# TemperatureZB.net
KiCad netlist of a schematic drawn in Altium Designer
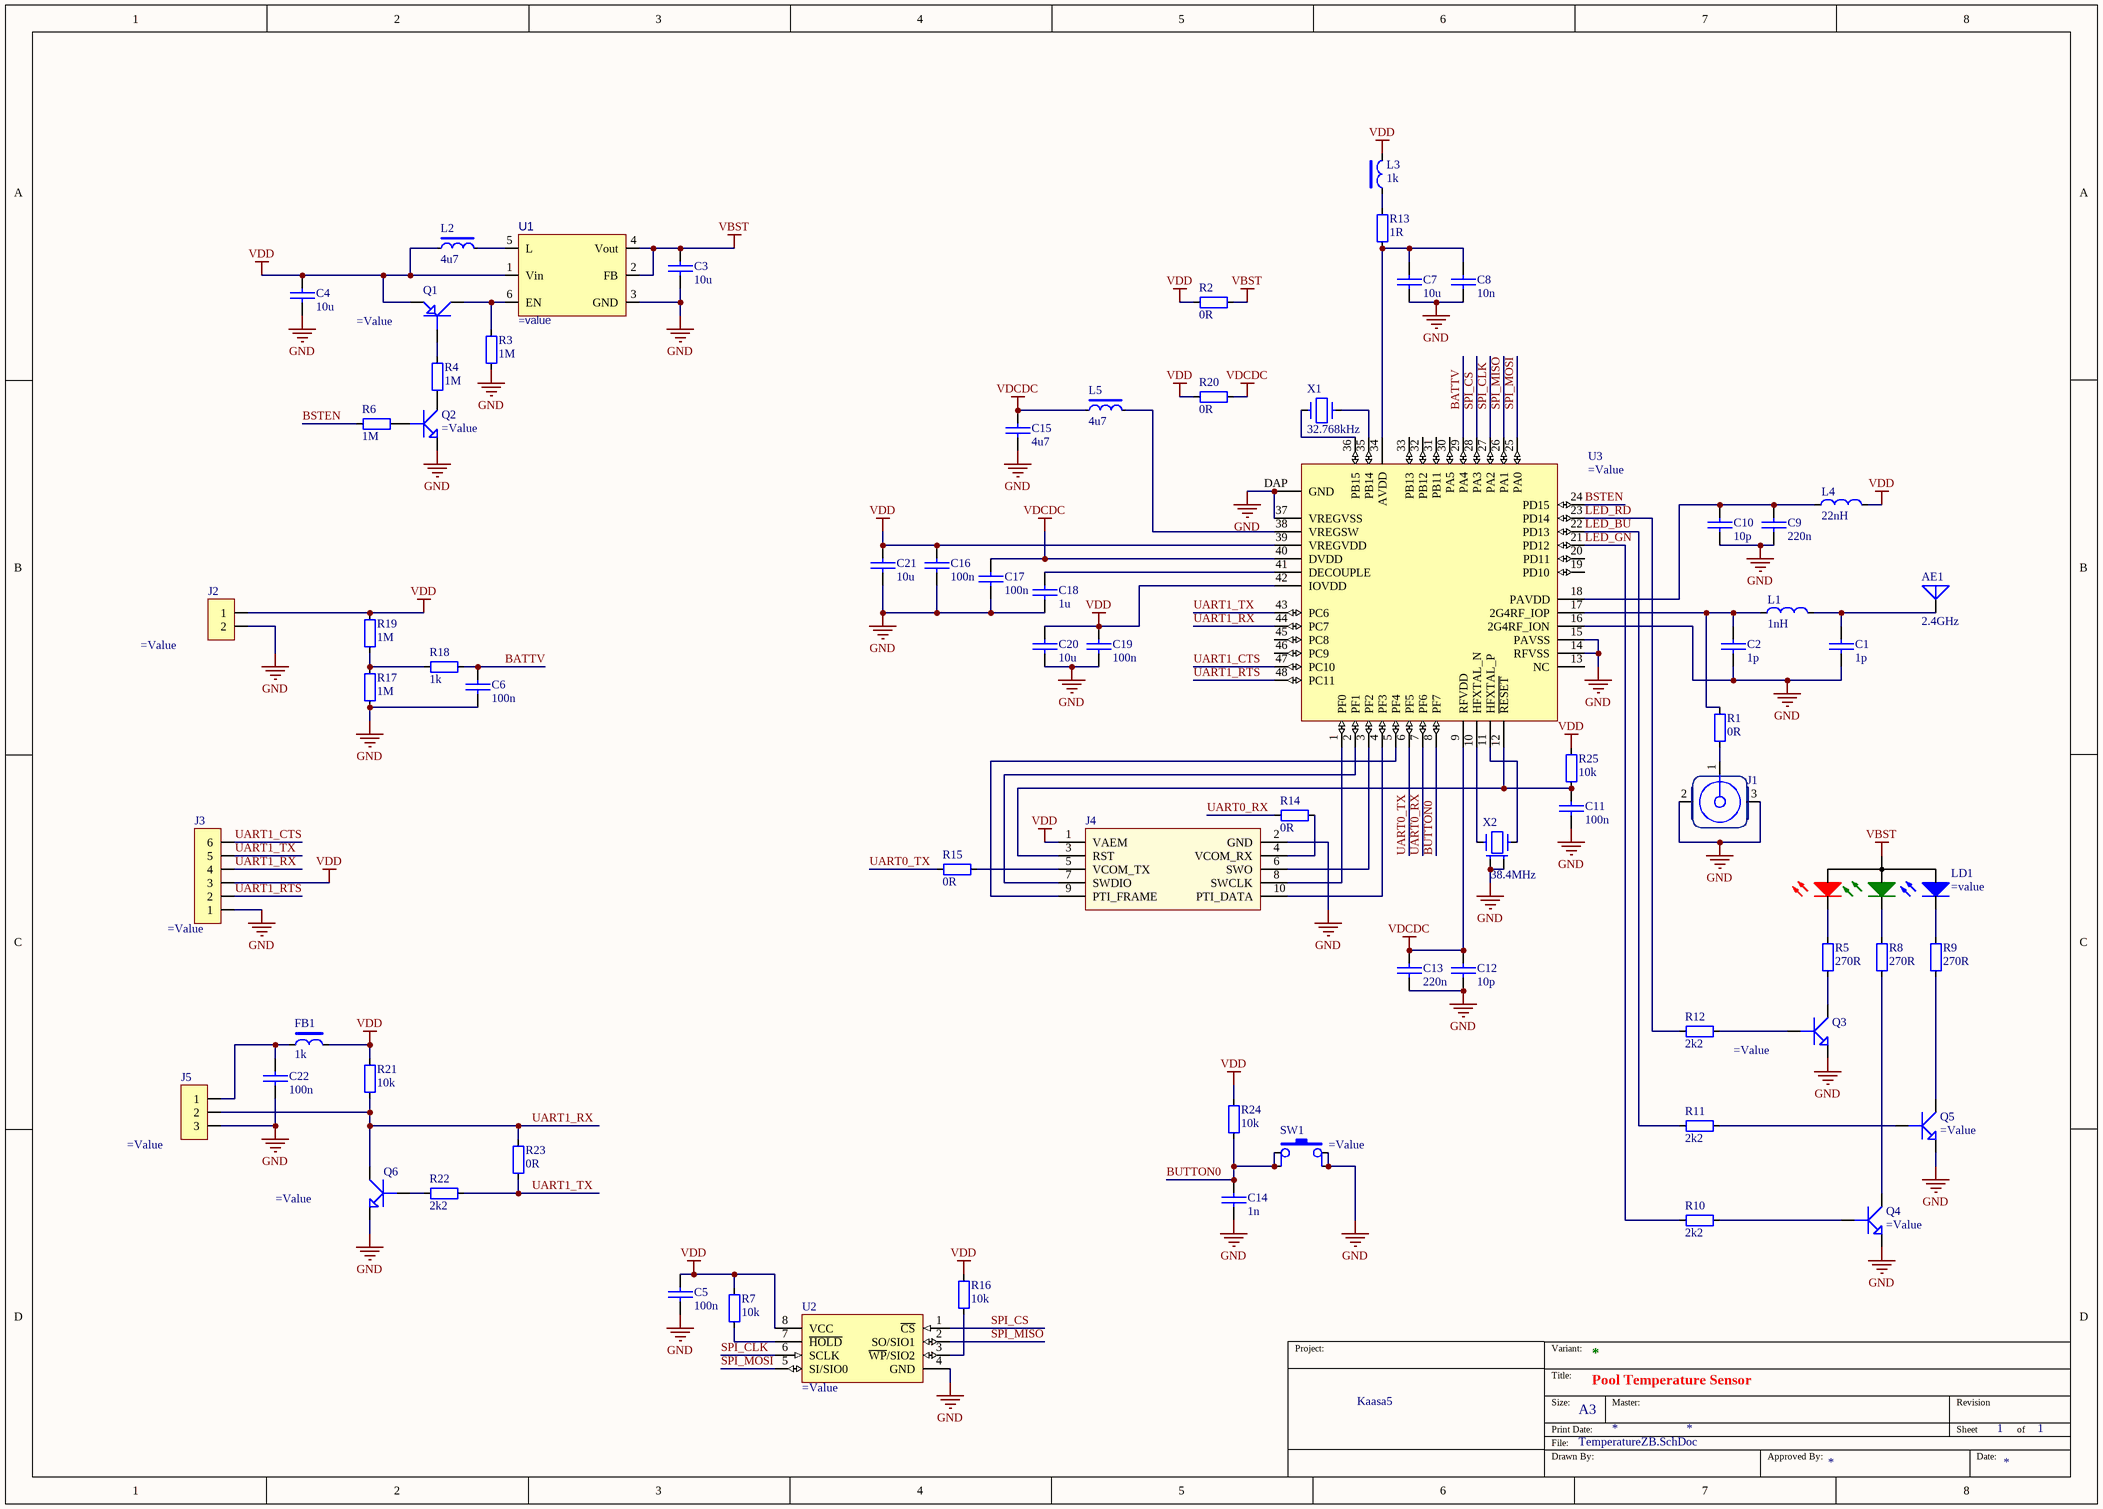
[diagram p0: TemperatureZB.SchDoc]

(export (version "E")
  (design (tool "Eeschema 10.0.6"))
  (components
    (comp (ref "AE1")
      (value "2.4GHz")
      (footprint "ANT2450AT45A100")
      (description "ANT SMD CER 1dB 3808")
      (fields
        (field (name "MANUFACTURER") "Johanson Technology Inc.")
        (field (name "PART NUMBER") "2450AT45A100E")
      )
      (libsource (lib "kaasa5") (part "AE_NORM"))
    )
    (comp (ref "C1")
      (value "1p")
      (footprint "CAPC1005X06N")
      (description "CAP SMD CER C0G/NPO ±0.1p 50V 0402")
      (fields (field (name "PART NUMBER") "CC0402BRNPO9BN1R0") (field (name "MANUFACTURER") "Yageo"))
      (libsource (lib "kaasa5") (part "C_NORM"))
    )
    (comp (ref "C2")
      (value "1p")
      (footprint "CAPC1005X06N")
      (description "CAP SMD CER C0G/NPO ±0.1p 50V 0402")
      (fields (field (name "PART NUMBER") "CC0402BRNPO9BN1R0") (field (name "MANUFACTURER") "Yageo"))
      (libsource (lib "kaasa5") (part "C_NORM"))
    )
    (comp (ref "C3")
      (value "10u")
      (footprint "CAPC1005X06N")
      (description "CAP SMD CER X5R 20% 6.3V 0402")
      (fields
        (field (name "PART NUMBER") "GRM155R60J106ME15D")
        (field (name "MANUFACTURER") "Murata Electronics")
      )
      (libsource (lib "kaasa5") (part "C_NORM"))
    )
    (comp (ref "C4")
      (value "10u")
      (footprint "CAPC1005X06N")
      (description "CAP SMD CER X5R 20% 6.3V 0402")
      (fields
        (field (name "PART NUMBER") "GRM155R60J106ME15D")
        (field (name "MANUFACTURER") "Murata Electronics")
      )
      (libsource (lib "kaasa5") (part "C_NORM"))
    )
    (comp (ref "C5")
      (value "100n")
      (footprint "CAPC1005X06N")
      (description "CAP SMD CER X7R 10% 16V 0402")
      (fields (field (name "PART NUMBER") "CC0402KRX7R7BB104") (field (name "MANUFACTURER") "Yageo"))
      (libsource (lib "kaasa5") (part "C_NORM"))
    )
    (comp (ref "C6")
      (value "100n")
      (footprint "CAPC1005X06N")
      (description "CAP SMD CER X7R 10% 16V 0402")
      (fields (field (name "MANUFACTURER") "Yageo") (field (name "PART NUMBER") "CC0402KRX7R7BB104"))
      (libsource (lib "kaasa5") (part "C_NORM"))
    )
    (comp (ref "C7")
      (value "10u")
      (footprint "CAPC1005X06N")
      (description "CAP SMD CER X5R 20% 6.3V 0402")
      (fields
        (field (name "PART NUMBER") "GRM155R60J106ME15D")
        (field (name "MANUFACTURER") "Murata Electronics")
      )
      (libsource (lib "kaasa5") (part "C_NORM"))
    )
    (comp (ref "C8")
      (value "10n")
      (footprint "CAPC1005X06N")
      (description "CAP SMD CER X7R 10% 50V 0402")
      (fields (field (name "PART NUMBER") "CC0402KRX7R9BB103") (field (name "MANUFACTURER") "Yageo"))
      (libsource (lib "kaasa5") (part "C_NORM"))
    )
    (comp (ref "C9")
      (value "220n")
      (footprint "CAPC1005X06N")
      (description "CAP SMD CER X7R 10% 16V 0402")
      (fields
        (field (name "PART NUMBER") "CL05B224KO5NNNC")
        (field (name "MANUFACTURER") "Samsung Electro-Mechanics")
      )
      (libsource (lib "kaasa5") (part "C_NORM"))
    )
    (comp (ref "C10")
      (value "10p")
      (footprint "CAPC1005X06N")
      (description "CAP SMD CER C0G/NPO 5% 50V 0402")
      (fields (field (name "PART NUMBER") "CC0402JRNPO9BN100") (field (name "MANUFACTURER") "Yageo"))
      (libsource (lib "kaasa5") (part "C_NORM"))
    )
    (comp (ref "C11")
      (value "100n")
      (footprint "CAPC1005X06N")
      (description "CAP SMD CER X7R 10% 16V 0402")
      (fields (field (name "PART NUMBER") "CC0402KRX7R7BB104") (field (name "MANUFACTURER") "Yageo"))
      (libsource (lib "kaasa5") (part "C_NORM"))
    )
    (comp (ref "C12")
      (value "10p")
      (footprint "CAPC1005X06N")
      (description "CAP SMD CER C0G/NPO 5% 50V 0402")
      (fields (field (name "PART NUMBER") "CC0402JRNPO9BN100") (field (name "MANUFACTURER") "Yageo"))
      (libsource (lib "kaasa5") (part "C_NORM"))
    )
    (comp (ref "C13")
      (value "220n")
      (footprint "CAPC1005X06N")
      (description "CAP SMD CER X7R 10% 16V 0402")
      (fields
        (field (name "PART NUMBER") "CL05B224KO5NNNC")
        (field (name "MANUFACTURER") "Samsung Electro-Mechanics")
      )
      (libsource (lib "kaasa5") (part "C_NORM"))
    )
    (comp (ref "C14")
      (value "1n")
      (footprint "CAPC1005X06N")
      (description "CAP SMD CER C0G/NPO 5% 50V 0402")
      (fields
        (field (name "PART NUMBER") "GRM1555C1H102JA01D")
        (field (name "MANUFACTURER") "Murata Electronics")
      )
      (libsource (lib "kaasa5") (part "C_NORM"))
    )
    (comp (ref "C15")
      (value "4u7")
      (footprint "CAPC1608X09N")
      (description "CAP SMD CER X7R 10% 6V3 0603")
      (fields
        (field (name "PART NUMBER") "CL10B475KQ8NQNC")
        (field (name "MANUFACTURER") "Samsung Electro-Mechanics")
      )
      (libsource (lib "kaasa5") (part "C_NORM"))
    )
    (comp (ref "C16")
      (value "100n")
      (footprint "CAPC1005X06N")
      (description "CAP SMD CER X7R 10% 16V 0402")
      (fields (field (name "PART NUMBER") "CC0402KRX7R7BB104") (field (name "MANUFACTURER") "Yageo"))
      (libsource (lib "kaasa5") (part "C_NORM"))
    )
    (comp (ref "C17")
      (value "100n")
      (footprint "CAPC1005X06N")
      (description "CAP SMD CER X7R 10% 16V 0402")
      (fields (field (name "PART NUMBER") "CC0402KRX7R7BB104") (field (name "MANUFACTURER") "Yageo"))
      (libsource (lib "kaasa5") (part "C_NORM"))
    )
    (comp (ref "C18")
      (value "1u")
      (footprint "CAPC1005X06N")
      (description "CAP SMD CER X7R 10% 6.3V 0402")
      (fields
        (field (name "PART NUMBER") "GRM155R70J105KA12J")
        (field (name "MANUFACTURER") "Murata Electronics")
      )
      (libsource (lib "kaasa5") (part "C_NORM"))
    )
    (comp (ref "C19")
      (value "100n")
      (footprint "CAPC1005X06N")
      (description "CAP SMD CER X7R 10% 16V 0402")
      (fields (field (name "PART NUMBER") "CC0402KRX7R7BB104") (field (name "MANUFACTURER") "Yageo"))
      (libsource (lib "kaasa5") (part "C_NORM"))
    )
    (comp (ref "C20")
      (value "10u")
      (footprint "CAPC1005X06N")
      (description "CAP SMD CER X5R 20% 6.3V 0402")
      (fields
        (field (name "PART NUMBER") "GRM155R60J106ME15D")
        (field (name "MANUFACTURER") "Murata Electronics")
      )
      (libsource (lib "kaasa5") (part "C_NORM"))
    )
    (comp (ref "C21")
      (value "10u")
      (footprint "CAPC1005X06N")
      (description "CAP SMD CER X5R 20% 6.3V 0402")
      (fields
        (field (name "PART NUMBER") "GRM155R60J106ME15D")
        (field (name "MANUFACTURER") "Murata Electronics")
      )
      (libsource (lib "kaasa5") (part "C_NORM"))
    )
    (comp (ref "C22")
      (value "100n")
      (footprint "CAPC1005X06N")
      (description "CAP SMD CER X7R 10% 16V 0402")
      (fields (field (name "MANUFACTURER") "Yageo") (field (name "PART NUMBER") "CC0402KRX7R7BB104"))
      (libsource (lib "kaasa5") (part "C_NORM"))
    )
    (comp (ref "FB1")
      (value "1k")
      (footprint "INDC1005X06N")
      (description "FER BEAD SMD ±25% 300mA 0402")
      (fields (field (name "PART NUMBER") "BK1005HS102-T") (field (name "MANUFACTURER") "Taiyo Yuden"))
      (libsource (lib "kaasa5") (part "FB_BEAD"))
    )
    (comp (ref "J1")
      (value "~")
      (footprint "U.FL-LP(V)-040")
      (description "CON SMD VERT RF U.FL")
      (fields
        (field (name "PART NUMBER") "1909763-1")
        (field (name "MANUFACTURER") "TE Connectivity AMP Connectors")
      )
      (libsource (lib "kaasa5") (part "J_CON_UFL"))
    )
    (comp (ref "J2")
      (value "~")
      (footprint "S2B-PH-SM4-TB")
      (description "CON SMD RIGHT ANGLE 100V 2A 2x5pin")
      (fields
        (field (name "MANUFACTURER") "JST Sales America Inc.")
        (field (name "PART NUMBER") "S2B-PH-SM4-TB(LF)(SN)")
      )
      (libsource (lib "kaasa5") (part "J_CON_SIL_2"))
    )
    (comp (ref "J3")
      (value "~")
      (footprint "HDR1X6")
      (description "CON THRU Vertical 1A Header 1x6pin")
      (fields (field (name "PART NUMBER") "68000-406HLF") (field (name "MANUFACTURER") "Amphenol 87"))
      (libsource (lib "kaasa5") (part "J_CON_SIL_6"))
    )
    (comp (ref "J4")
      (value "~")
      (footprint "HDR127MM2X5(noPilot)")
      (description "CON SMD 1A 2x5pin")
      (fields
        (field (name "PART NUMBER") "GRPB052VWQS-RC")
        (field (name "MANUFACTURER") "Sullins Connector Solutions")
      )
      (libsource (lib "kaasa5") (part "HDR_MINI_SIMP_DEBUG"))
    )
    (comp (ref "J5")
      (value "~")
      (footprint "S3B-PH-SM4-TB")
      (description "CON SMD RIGHT ANGLE 100V 2A Header 1x3pin")
      (fields
        (field (name "PART NUMBER") "S3B-PH-SM4-TB(LF)(SN)")
        (field (name "MANUFACTURER") "JST Sales America Inc.")
      )
      (libsource (lib "kaasa5") (part "J_CON_SIL_3"))
    )
    (comp (ref "L1")
      (value "1nH")
      (footprint "INDC1005X06N")
      (description "IND SMD UnShielded W/W 5% 1.36A 0402")
      (fields (field (name "PART NUMBER") "AISC-0402-1N0J-T") (field (name "MANUFACTURER") "Abracon LLC"))
      (libsource (lib "kaasa5") (part "L_AIR"))
    )
    (comp (ref "L2")
      (value "4u7")
      (footprint "INDC2020X12N")
      (description "IND SMD UnShielded W/W 5% 750mA 2010")
      (fields (field (name "MANUFACTURER") "Taiyo Yuden") (field (name "PART NUMBER") "NRV2012T4R7MGF"))
      (libsource (lib "kaasa5") (part "L_FER"))
    )
    (comp (ref "L3")
      (value "1k")
      (footprint "INDC1005X06N")
      (description "FER BEAD SMD ±25% 300mA 0402")
      (fields (field (name "PART NUMBER") "BK1005HS102-T") (field (name "MANUFACTURER") "Taiyo Yuden"))
      (libsource (lib "") (part "FB_BEAD_1"))
    )
    (comp (ref "L4")
      (value "22nH")
      (footprint "INDC1005X06N")
      (description "IND SMD UnShielded Multi-Layer 5% 350mA 0402")
      (fields
        (field (name "PART NUMBER") "LQG15HS22NJ02D")
        (field (name "MANUFACTURER") "Murata Electronics")
      )
      (libsource (lib "kaasa5") (part "L_AIR"))
    )
    (comp (ref "L5")
      (value "4u7")
      (footprint "INDC2020X12N")
      (description "IND SMD UnShielded W/W 5% 750mA 2010")
      (fields (field (name "PART NUMBER") "NRV2012T4R7MGF") (field (name "MANUFACTURER") "Taiyo Yuden"))
      (libsource (lib "kaasa5") (part "L_FER"))
    )
    (comp (ref "LD1")
      (value "~")
      (footprint "LEDM3528X190-4N")
      (description "LED SMD 540mcd Red, 1600mcd Green, 350mcd Blue 4PLCC")
      (fields (field (name "MANUFACTURER") "Broadcom Limited") (field (name "PART NUMBER") "ASMB-MTB1-0A3A2"))
      (libsource (lib "kaasa5") (part "LED_RGB_COM_A"))
    )
    (comp (ref "Q1")
      (value "~")
      (footprint "SOT95P230X110-3N")
      (description "TRANS SMD BJT PNP 40V 0.2A SOT23")
      (fields (field (name "MANUFACTURER") "Nexperia USA Inc.") (field (name "PART NUMBER") "MMBT3906,215"))
      (libsource (lib "kaasa5") (part "Q_PNP"))
    )
    (comp (ref "Q2")
      (value "~")
      (footprint "SOT95P230X110-3N")
      (description "TRANS SMD BJT NPN 40V 0.2A SOT23")
      (fields (field (name "MANUFACTURER") "Nexperia USA Inc.") (field (name "PART NUMBER") "MMBT3904,215"))
      (libsource (lib "kaasa5") (part "Q_NPN"))
    )
    (comp (ref "Q3")
      (value "~")
      (footprint "SOT95P230X110-3N")
      (description "TRANS SMD BJT NPN 40V 0.2A SOT23")
      (fields (field (name "MANUFACTURER") "Nexperia USA Inc.") (field (name "PART NUMBER") "MMBT3904,215"))
      (libsource (lib "kaasa5") (part "Q_NPN"))
    )
    (comp (ref "Q4")
      (value "~")
      (footprint "SOT95P230X110-3N")
      (description "TRANS SMD BJT NPN 40V 0.2A SOT23")
      (fields (field (name "MANUFACTURER") "Nexperia USA Inc.") (field (name "PART NUMBER") "MMBT3904,215"))
      (libsource (lib "kaasa5") (part "Q_NPN"))
    )
    (comp (ref "Q5")
      (value "~")
      (footprint "SOT95P230X110-3N")
      (description "TRANS SMD BJT NPN 40V 0.2A SOT23")
      (fields (field (name "MANUFACTURER") "Nexperia USA Inc.") (field (name "PART NUMBER") "MMBT3904,215"))
      (libsource (lib "kaasa5") (part "Q_NPN"))
    )
    (comp (ref "Q6")
      (value "~")
      (footprint "SOT95P230X110-3N")
      (description "TRANS SMD BJT NPN 40V 0.2A SOT23")
      (fields (field (name "MANUFACTURER") "Nexperia USA Inc.") (field (name "PART NUMBER") "MMBT3904,215"))
      (libsource (lib "kaasa5") (part "Q_NPN"))
    )
    (comp (ref "R1")
      (value "0R")
      (footprint "RESC1005X04N")
      (description "RES SMD Think Film 1% 1/16W 1A 100V 0402")
      (fields (field (name "PART NUMBER") "RC0402FR-070RL") (field (name "MANUFACTURER") "Yageo"))
      (libsource (lib "kaasa5") (part "R_NORM"))
    )
    (comp (ref "R2")
      (value "0R")
      (footprint "RESC1005X04N")
      (description "RES SMD Think Film 1% 1/16W 1A 100V 0402")
      (fields (field (name "PART NUMBER") "RC0402FR-070RL") (field (name "MANUFACTURER") "Yageo"))
      (libsource (lib "kaasa5") (part "R_NORM"))
    )
    (comp (ref "R3")
      (value "1M")
      (footprint "RESC1005X04N")
      (description "RES SMD Think Film 1% 1/16W 50V 0402")
      (fields (field (name "PART NUMBER") "RC0402FR-071ML") (field (name "MANUFACTURER") "Yageo"))
      (libsource (lib "kaasa5") (part "R_NORM"))
    )
    (comp (ref "R4")
      (value "1M")
      (footprint "RESC1005X04N")
      (description "RES SMD Think Film 1% 1/16W 50V 0402")
      (fields (field (name "MANUFACTURER") "Yageo") (field (name "PART NUMBER") "RC0402FR-071ML"))
      (libsource (lib "kaasa5") (part "R_NORM"))
    )
    (comp (ref "R5")
      (value "270R")
      (footprint "RESC1005X04N")
      (description "RES SMD Think Film 1% 1/16W 100V 0402")
      (fields (field (name "PART NUMBER") "RC0402FR-07270RL") (field (name "MANUFACTURER") "Yageo"))
      (libsource (lib "kaasa5") (part "R_NORM"))
    )
    (comp (ref "R6")
      (value "1M")
      (footprint "RESC1005X04N")
      (description "RES SMD Think Film 1% 1/16W 50V 0402")
      (fields (field (name "MANUFACTURER") "Yageo") (field (name "PART NUMBER") "RC0402FR-071ML"))
      (libsource (lib "kaasa5") (part "R_NORM"))
    )
    (comp (ref "R7")
      (value "10k")
      (footprint "RESC1005X04N")
      (description "RES SMD Think Film 1% 1/16W 100V 0402")
      (fields (field (name "PART NUMBER") "RC0402FR-0710KL") (field (name "MANUFACTURER") "Yageo"))
      (libsource (lib "kaasa5") (part "R_NORM"))
    )
    (comp (ref "R8")
      (value "270R")
      (footprint "RESC1005X04N")
      (description "RES SMD Think Film 1% 1/16W 100V 0402")
      (fields (field (name "PART NUMBER") "RC0402FR-07270RL") (field (name "MANUFACTURER") "Yageo"))
      (libsource (lib "kaasa5") (part "R_NORM"))
    )
    (comp (ref "R9")
      (value "270R")
      (footprint "RESC1005X04N")
      (description "RES SMD Think Film 1% 1/16W 100V 0402")
      (fields (field (name "PART NUMBER") "RC0402FR-07270RL") (field (name "MANUFACTURER") "Yageo"))
      (libsource (lib "kaasa5") (part "R_NORM"))
    )
    (comp (ref "R10")
      (value "2k2")
      (footprint "RESC1005X04N")
      (description "RES SMD Think Film 1% 1/16W 50V 0402")
      (fields (field (name "MANUFACTURER") "Yageo") (field (name "PART NUMBER") "RC0402FR-072K2L"))
      (libsource (lib "kaasa5") (part "R_NORM"))
    )
    (comp (ref "R11")
      (value "2k2")
      (footprint "RESC1005X04N")
      (description "RES SMD Think Film 1% 1/16W 50V 0402")
      (fields (field (name "MANUFACTURER") "Yageo") (field (name "PART NUMBER") "RC0402FR-072K2L"))
      (libsource (lib "kaasa5") (part "R_NORM"))
    )
    (comp (ref "R12")
      (value "2k2")
      (footprint "RESC1005X04N")
      (description "RES SMD Think Film 1% 1/16W 50V 0402")
      (fields (field (name "MANUFACTURER") "Yageo") (field (name "PART NUMBER") "RC0402FR-072K2L"))
      (libsource (lib "kaasa5") (part "R_NORM"))
    )
    (comp (ref "R13")
      (value "1R")
      (footprint "RESC1005X04N")
      (description "RES SMD Think Film 1% 1/16W 100V 0402")
      (fields (field (name "PART NUMBER") "RC0402FR-071RL") (field (name "MANUFACTURER") "Yageo"))
      (libsource (lib "kaasa5") (part "R_NORM"))
    )
    (comp (ref "R14")
      (value "0R")
      (footprint "RESC1005X04N")
      (description "RES SMD Think Film 1% 1/16W 1A 100V 0402")
      (fields (field (name "PART NUMBER") "RC0402FR-070RL") (field (name "MANUFACTURER") "Yageo"))
      (libsource (lib "kaasa5") (part "R_NORM"))
    )
    (comp (ref "R15")
      (value "0R")
      (footprint "RESC1005X04N")
      (description "RES SMD Think Film 1% 1/16W 1A 100V 0402")
      (fields (field (name "PART NUMBER") "RC0402FR-070RL") (field (name "MANUFACTURER") "Yageo"))
      (libsource (lib "kaasa5") (part "R_NORM"))
    )
    (comp (ref "R16")
      (value "10k")
      (footprint "RESC1005X04N")
      (description "RES SMD Think Film 1% 1/16W 100V 0402")
      (fields (field (name "PART NUMBER") "RC0402FR-0710KL") (field (name "MANUFACTURER") "Yageo"))
      (libsource (lib "kaasa5") (part "R_NORM"))
    )
    (comp (ref "R17")
      (value "1M")
      (footprint "RESC1005X04N")
      (description "RES SMD Think Film 1% 1/16W 50V 0402")
      (fields (field (name "MANUFACTURER") "Yageo") (field (name "PART NUMBER") "RC0402FR-071ML"))
      (libsource (lib "kaasa5") (part "R_NORM"))
    )
    (comp (ref "R18")
      (value "1k")
      (footprint "RESC1005X04N")
      (description "RES SMD Think Film 1% 1/16W 100V 0402")
      (fields (field (name "PART NUMBER") "RC0402FR-071KL") (field (name "MANUFACTURER") "Yageo"))
      (libsource (lib "kaasa5") (part "R_NORM"))
    )
    (comp (ref "R19")
      (value "1M")
      (footprint "RESC1005X04N")
      (description "RES SMD Think Film 1% 1/16W 50V 0402")
      (fields (field (name "MANUFACTURER") "Yageo") (field (name "PART NUMBER") "RC0402FR-071ML"))
      (libsource (lib "kaasa5") (part "R_NORM"))
    )
    (comp (ref "R20")
      (value "0R")
      (footprint "RESC1005X04N")
      (description "RES SMD Think Film 1% 1/16W 1A 100V 0402")
      (fields (field (name "PART NUMBER") "RC0402FR-070RL") (field (name "MANUFACTURER") "Yageo"))
      (libsource (lib "kaasa5") (part "R_NORM"))
    )
    (comp (ref "R21")
      (value "10k")
      (footprint "RESC1005X04N")
      (description "RES SMD Think Film 1% 1/16W 100V 0402")
      (fields (field (name "MANUFACTURER") "Yageo") (field (name "PART NUMBER") "RC0402FR-0710KL"))
      (libsource (lib "kaasa5") (part "R_NORM"))
    )
    (comp (ref "R22")
      (value "2k2")
      (footprint "RESC1005X04N")
      (description "RES SMD Think Film 1% 1/16W 50V 0402")
      (fields (field (name "MANUFACTURER") "Yageo") (field (name "PART NUMBER") "RC0402FR-072K2L"))
      (libsource (lib "kaasa5") (part "R_NORM"))
    )
    (comp (ref "R23")
      (value "0R")
      (footprint "RESC1005X04N")
      (description "RES SMD Think Film 1% 1/16W 1A 100V 0402")
      (fields (field (name "PART NUMBER") "RC0402FR-070RL") (field (name "MANUFACTURER") "Yageo"))
      (libsource (lib "kaasa5") (part "R_NORM"))
    )
    (comp (ref "R24")
      (value "10k")
      (footprint "RESC1005X04N")
      (description "RES SMD Think Film 1% 1/16W 100V 0402")
      (fields (field (name "PART NUMBER") "RC0402FR-0710KL") (field (name "MANUFACTURER") "Yageo"))
      (libsource (lib "kaasa5") (part "R_NORM"))
    )
    (comp (ref "R25")
      (value "10k")
      (footprint "RESC1005X04N")
      (description "RES SMD Think Film 1% 1/16W 100V 0402")
      (fields (field (name "PART NUMBER") "RC0402FR-0710KL") (field (name "MANUFACTURER") "Yageo"))
      (libsource (lib "kaasa5") (part "R_NORM"))
    )
    (comp (ref "SW1")
      (value "~")
      (footprint "SW450P600x600-4N")
      (description "SWITCH SMD TACTILE PUSH BUTTON SPST-NO 12V 50mA GULLWING")
      (fields
        (field (name "MANUFACTURER") "C&K Components")
        (field (name "PART NUMBER") "PTS645SK50SMTR92 LFS")
      )
      (libsource (lib "kaasa5") (part "SW_PB_4PIN"))
    )
    (comp (ref "U1")
      (value "~")
      (footprint "SOT363-6N")
      (description "IC SMD BOOST CONV 5V 200mA SC70-6")
      (fields (field (name "PART NUMBER") "TPS61222DCKR") (field (name "MANUFACTURER") "Texas Instruments"))
      (libsource (lib "kaasa5") (part "TPS6122x"))
    )
    (comp (ref "U2")
      (value "~")
      (footprint "SOIC127P600X175-8N")
      (description "IC SMD FLASH SPI 8Mb (1M x 8) SOP8")
      (fields (field (name "MANUFACTURER") "Macronix") (field (name "PART NUMBER") "MX25R8035FM1IH1"))
      (libsource (lib "kaasa5") (part "MX25Rxx35F"))
    )
    (comp (ref "U3")
      (value "~")
      (footprint "QFN50P700X700X80-4846N")
      (description "SoC Bluetooth CORTEX-M4 48MHz 1Mb Flash 256kb RAM QFN48")
      (fields
        (field (name "PART NUMBER") "EFR32MG12P332F1024GM48-B")
        (field (name "MANUFACTURER") "Silicon Labs")
      )
      (libsource (lib "kaasa5") (part "EFRMG1xxx2F256GM48-C0"))
    )
    (comp (ref "X1")
      (value "32.768kHz")
      (footprint "XTAL32X15X09")
      (description "XTL SMD ±20ppm 12.5pF SMD-2")
      (fields (field (name "PART NUMBER") "FC-135 32.7680KA-A5") (field (name "MANUFACTURER") "EPSON"))
      (libsource (lib "kaasa5") (part "X_CRYSTAL"))
    )
    (comp (ref "X2")
      (value "38.4MHz")
      (footprint "LCCS185P320X250X80-4N")
      (description "XTL SMD ±10ppm  8.5pF SMD-4")
      (fields (field (name "PART NUMBER") "TSX-3225 38.4000MF10Z-AS3") (field (name "MANUFACTURER") "EPSON"))
      (libsource (lib "kaasa5") (part "X_CRYSTAL4PIN_13"))
    )
  )
  (nets
    (net (code "1") (name "/BATTV") (class "Default")
      (node (ref "C6") (pin "1") (pintype "passive"))
      (node (ref "R18") (pin "2") (pintype "passive"))
      (node (ref "U3") (pin "29") (pinfunction "PA4_29") (pintype "bidirectional"))
    )
    (net (code "2") (name "/BSTEN") (class "Default")
      (node (ref "R6") (pin "1") (pintype "passive"))
      (node (ref "U3") (pin "24") (pinfunction "PD15_24") (pintype "bidirectional"))
    )
    (net (code "3") (name "/BUTTON0") (class "Default")
      (node (ref "C14") (pin "1") (pintype "passive"))
      (node (ref "R24") (pin "2") (pintype "passive"))
      (node (ref "SW1") (pin "1") (pintype "passive"))
      (node (ref "SW1") (pin "3") (pinfunction "3_3") (pintype "passive"))
      (node (ref "U3") (pin "8") (pinfunction "PF7_8") (pintype "bidirectional"))
    )
    (net (code "4") (name "/LED_BU") (class "Default")
      (node (ref "R11") (pin "1") (pintype "passive"))
      (node (ref "U3") (pin "22") (pinfunction "PD13_22") (pintype "bidirectional"))
    )
    (net (code "5") (name "/LED_GN") (class "Default")
      (node (ref "R10") (pin "1") (pintype "passive"))
      (node (ref "U3") (pin "21") (pinfunction "PD12_21") (pintype "bidirectional"))
    )
    (net (code "6") (name "/LED_RD") (class "Default")
      (node (ref "R12") (pin "1") (pintype "passive"))
      (node (ref "U3") (pin "23") (pinfunction "PD14_23") (pintype "bidirectional"))
    )
    (net (code "7") (name "/SPI_CLK") (class "Default")
      (node (ref "U2") (pin "6") (pinfunction "SCLK_6") (pintype "input"))
      (node (ref "U3") (pin "27") (pinfunction "PA2_27") (pintype "bidirectional"))
    )
    (net (code "8") (name "/SPI_CS") (class "Default")
      (node (ref "U2") (pin "1") (pinfunction "~{CS}_1") (pintype "input"))
      (node (ref "U3") (pin "28") (pinfunction "PA3_28") (pintype "bidirectional"))
    )
    (net (code "9") (name "/SPI_MISO") (class "Default")
      (node (ref "U2") (pin "2") (pinfunction "SO/SIO1_2") (pintype "bidirectional"))
      (node (ref "U3") (pin "26") (pinfunction "PA1_26") (pintype "bidirectional"))
    )
    (net (code "10") (name "/SPI_MOSI") (class "Default")
      (node (ref "U2") (pin "5") (pinfunction "SI/SIO0_5") (pintype "bidirectional"))
      (node (ref "U3") (pin "25") (pinfunction "PA0_25") (pintype "bidirectional"))
    )
    (net (code "11") (name "/UART0_RX") (class "Default")
      (node (ref "R14") (pin "2") (pintype "passive"))
      (node (ref "U3") (pin "7") (pinfunction "PF6_7") (pintype "bidirectional"))
    )
    (net (code "12") (name "/UART0_TX") (class "Default")
      (node (ref "R15") (pin "1") (pintype "passive"))
      (node (ref "U3") (pin "6") (pinfunction "PF5_6") (pintype "bidirectional"))
    )
    (net (code "13") (name "/UART1_CTS") (class "Default")
      (node (ref "J3") (pin "6") (pinfunction "6_6") (pintype "passive"))
      (node (ref "U3") (pin "47") (pinfunction "PC10_47") (pintype "bidirectional"))
    )
    (net (code "14") (name "/UART1_RTS") (class "Default")
      (node (ref "J3") (pin "2") (pinfunction "2_2") (pintype "passive"))
      (node (ref "U3") (pin "48") (pinfunction "PC11_48") (pintype "bidirectional"))
    )
    (net (code "15") (name "/UART1_RX") (class "Default")
      (node (ref "J3") (pin "4") (pinfunction "4_4") (pintype "passive"))
      (node (ref "J5") (pin "2") (pinfunction "2_2") (pintype "passive"))
      (node (ref "Q6") (pin "3") (pinfunction "C_3") (pintype "passive"))
      (node (ref "R21") (pin "1") (pintype "passive"))
      (node (ref "R23") (pin "2") (pintype "passive"))
      (node (ref "U3") (pin "44") (pinfunction "PC7_44") (pintype "bidirectional"))
    )
    (net (code "16") (name "/UART1_TX") (class "Default")
      (node (ref "J3") (pin "5") (pinfunction "5_5") (pintype "passive"))
      (node (ref "R22") (pin "1") (pintype "passive"))
      (node (ref "R23") (pin "1") (pintype "passive"))
      (node (ref "U3") (pin "43") (pinfunction "PC6_43") (pintype "bidirectional"))
    )
    (net (code "17") (name "GND") (class "Default")
      (node (ref "C1") (pin "2") (pintype "passive"))
      (node (ref "C10") (pin "2") (pintype "passive"))
      (node (ref "C11") (pin "2") (pintype "passive"))
      (node (ref "C12") (pin "2") (pintype "passive"))
      (node (ref "C13") (pin "2") (pintype "passive"))
      (node (ref "C14") (pin "2") (pintype "passive"))
      (node (ref "C15") (pin "1") (pintype "passive"))
      (node (ref "C16") (pin "1") (pintype "passive"))
      (node (ref "C17") (pin "2") (pintype "passive"))
      (node (ref "C18") (pin "2") (pintype "passive"))
      (node (ref "C19") (pin "2") (pintype "passive"))
      (node (ref "C2") (pin "2") (pintype "passive"))
      (node (ref "C20") (pin "2") (pintype "passive"))
      (node (ref "C21") (pin "2") (pintype "passive"))
      (node (ref "C22") (pin "2") (pintype "passive"))
      (node (ref "C3") (pin "1") (pintype "passive"))
      (node (ref "C4") (pin "1") (pintype "passive"))
      (node (ref "C5") (pin "2") (pintype "passive"))
      (node (ref "C6") (pin "2") (pintype "passive"))
      (node (ref "C7") (pin "1") (pintype "passive"))
      (node (ref "C8") (pin "2") (pintype "passive"))
      (node (ref "C9") (pin "2") (pintype "passive"))
      (node (ref "J1") (pin "2") (pinfunction "GND_2") (pintype "power_in"))
      (node (ref "J1") (pin "3") (pinfunction "GND_3") (pintype "power_in"))
      (node (ref "J2") (pin "2") (pinfunction "2_2") (pintype "passive"))
      (node (ref "J3") (pin "1") (pinfunction "1_1") (pintype "passive"))
      (node (ref "J4") (pin "2") (pinfunction "GND_2") (pintype "passive"))
      (node (ref "J5") (pin "3") (pinfunction "3_3") (pintype "passive"))
      (node (ref "Q2") (pin "2") (pinfunction "E_2") (pintype "passive"))
      (node (ref "Q3") (pin "2") (pinfunction "E_2") (pintype "passive"))
      (node (ref "Q4") (pin "2") (pinfunction "E_2") (pintype "passive"))
      (node (ref "Q5") (pin "2") (pinfunction "E_2") (pintype "passive"))
      (node (ref "Q6") (pin "2") (pinfunction "E_2") (pintype "passive"))
      (node (ref "R17") (pin "1") (pintype "passive"))
      (node (ref "R3") (pin "2") (pintype "passive"))
      (node (ref "SW1") (pin "2") (pintype "passive"))
      (node (ref "SW1") (pin "4") (pinfunction "4_4") (pintype "passive"))
      (node (ref "U1") (pin "3") (pinfunction "GND_3") (pintype "passive"))
      (node (ref "U2") (pin "4") (pinfunction "GND_4") (pintype "power_in"))
      (node (ref "U3") (pin "14") (pinfunction "RFVSS_14") (pintype "power_in"))
      (node (ref "U3") (pin "15") (pinfunction "PAVSS_15") (pintype "power_in"))
      (node (ref "U3") (pin "16") (pinfunction "2G4RF_ION_16") (pintype "passive"))
      (node (ref "U3") (pin "37") (pinfunction "VREGVSS_37") (pintype "power_in"))
      (node (ref "U3") (pin "DAP") (pinfunction "GND_DAP") (pintype "passive"))
      (node (ref "X2") (pin "2") (pinfunction "2_2") (pintype "passive"))
      (node (ref "X2") (pin "4") (pinfunction "4_4") (pintype "passive"))
    )
    (net (code "18") (name "Net-(AE1-Pad1)") (class "Default")
      (node (ref "AE1") (pin "1") (pintype "passive"))
      (node (ref "C1") (pin "1") (pintype "passive"))
      (node (ref "L1") (pin "2") (pintype "passive"))
    )
    (net (code "19") (name "Net-(C22-Pad1)") (class "Default")
      (node (ref "C22") (pin "1") (pintype "passive"))
      (node (ref "FB1") (pin "2") (pintype "passive"))
      (node (ref "J5") (pin "1") (pinfunction "1_1") (pintype "passive"))
    )
    (net (code "20") (name "Net-(J1-Signal)") (class "Default")
      (node (ref "J1") (pin "1") (pinfunction "Signal_1") (pintype "passive"))
      (node (ref "R1") (pin "2") (pintype "passive"))
    )
    (net (code "21") (name "Net-(J4-PTI_DATA)") (class "Default")
      (node (ref "J4") (pin "10") (pinfunction "PTI_DATA_10") (pintype "passive"))
      (node (ref "U3") (pin "4") (pinfunction "PF3_4") (pintype "bidirectional"))
    )
    (net (code "22") (name "Net-(J4-PTI_FRAME)") (class "Default")
      (node (ref "J4") (pin "9") (pinfunction "PTI_FRAME_9") (pintype "passive"))
      (node (ref "U3") (pin "5") (pinfunction "PF4_5") (pintype "bidirectional"))
    )
    (net (code "23") (name "Net-(J4-RST)") (class "Default")
      (node (ref "C11") (pin "1") (pintype "passive"))
      (node (ref "J4") (pin "3") (pinfunction "RST_3") (pintype "passive"))
      (node (ref "R25") (pin "1") (pintype "passive"))
      (node (ref "U3") (pin "12") (pinfunction "~{RESET}_12") (pintype "passive"))
    )
    (net (code "24") (name "Net-(J4-SWCLK)") (class "Default")
      (node (ref "J4") (pin "8") (pinfunction "SWCLK_8") (pintype "passive"))
      (node (ref "U3") (pin "1") (pinfunction "PF0_1") (pintype "bidirectional"))
    )
    (net (code "25") (name "Net-(J4-SWDIO)") (class "Default")
      (node (ref "J4") (pin "7") (pinfunction "SWDIO_7") (pintype "passive"))
      (node (ref "U3") (pin "2") (pinfunction "PF1_2") (pintype "bidirectional"))
    )
    (net (code "26") (name "Net-(J4-SWO)") (class "Default")
      (node (ref "J4") (pin "6") (pinfunction "SWO_6") (pintype "passive"))
      (node (ref "U3") (pin "3") (pinfunction "PF2_3") (pintype "bidirectional"))
    )
    (net (code "27") (name "Net-(J4-VCOM_RX)") (class "Default")
      (node (ref "J4") (pin "4") (pinfunction "VCOM_RX_4") (pintype "passive"))
      (node (ref "R14") (pin "1") (pintype "passive"))
    )
    (net (code "28") (name "Net-(J4-VCOM_TX)") (class "Default")
      (node (ref "J4") (pin "5") (pinfunction "VCOM_TX_5") (pintype "passive"))
      (node (ref "R15") (pin "2") (pintype "passive"))
    )
    (net (code "29") (name "Net-(L3-Pad1)") (class "Default")
      (node (ref "L3") (pin "1") (pintype "passive"))
      (node (ref "R13") (pin "2") (pintype "passive"))
    )
    (net (code "30") (name "Net-(LD1-K_BU)") (class "Default")
      (node (ref "LD1") (pin "3") (pinfunction "K_BU_3") (pintype "power_in"))
      (node (ref "R9") (pin "1") (pintype "passive"))
    )
    (net (code "31") (name "Net-(LD1-K_GR)") (class "Default")
      (node (ref "LD1") (pin "2") (pinfunction "K_GR_2") (pintype "passive"))
      (node (ref "R8") (pin "1") (pintype "passive"))
    )
    (net (code "32") (name "Net-(LD1-K_RD)") (class "Default")
      (node (ref "LD1") (pin "1") (pinfunction "K_RD_1") (pintype "power_in"))
      (node (ref "R5") (pin "1") (pintype "passive"))
    )
    (net (code "33") (name "Net-(Q1-B)") (class "Default")
      (node (ref "Q1") (pin "1") (pinfunction "B_1") (pintype "passive"))
      (node (ref "R4") (pin "2") (pintype "passive"))
    )
    (net (code "34") (name "Net-(Q1-C)") (class "Default")
      (node (ref "Q1") (pin "3") (pinfunction "C_3") (pintype "passive"))
      (node (ref "R3") (pin "1") (pintype "passive"))
      (node (ref "U1") (pin "6") (pinfunction "EN_6") (pintype "passive"))
    )
    (net (code "35") (name "Net-(Q2-B)") (class "Default")
      (node (ref "Q2") (pin "1") (pinfunction "B_1") (pintype "passive"))
      (node (ref "R6") (pin "2") (pintype "passive"))
    )
    (net (code "36") (name "Net-(Q2-C)") (class "Default")
      (node (ref "Q2") (pin "3") (pinfunction "C_3") (pintype "passive"))
      (node (ref "R4") (pin "1") (pintype "passive"))
    )
    (net (code "37") (name "Net-(Q3-B)") (class "Default")
      (node (ref "Q3") (pin "1") (pinfunction "B_1") (pintype "passive"))
      (node (ref "R12") (pin "2") (pintype "passive"))
    )
    (net (code "38") (name "Net-(Q3-C)") (class "Default")
      (node (ref "Q3") (pin "3") (pinfunction "C_3") (pintype "passive"))
      (node (ref "R5") (pin "2") (pintype "passive"))
    )
    (net (code "39") (name "Net-(Q4-B)") (class "Default")
      (node (ref "Q4") (pin "1") (pinfunction "B_1") (pintype "passive"))
      (node (ref "R10") (pin "2") (pintype "passive"))
    )
    (net (code "40") (name "Net-(Q4-C)") (class "Default")
      (node (ref "Q4") (pin "3") (pinfunction "C_3") (pintype "passive"))
      (node (ref "R8") (pin "2") (pintype "passive"))
    )
    (net (code "41") (name "Net-(Q5-B)") (class "Default")
      (node (ref "Q5") (pin "1") (pinfunction "B_1") (pintype "passive"))
      (node (ref "R11") (pin "2") (pintype "passive"))
    )
    (net (code "42") (name "Net-(Q5-C)") (class "Default")
      (node (ref "Q5") (pin "3") (pinfunction "C_3") (pintype "passive"))
      (node (ref "R9") (pin "2") (pintype "passive"))
    )
    (net (code "43") (name "Net-(Q6-B)") (class "Default")
      (node (ref "Q6") (pin "1") (pinfunction "B_1") (pintype "passive"))
      (node (ref "R22") (pin "2") (pintype "passive"))
    )
    (net (code "44") (name "Net-(R17-Pad2)") (class "Default")
      (node (ref "R17") (pin "2") (pintype "passive"))
      (node (ref "R18") (pin "1") (pintype "passive"))
      (node (ref "R19") (pin "1") (pintype "passive"))
    )
    (net (code "45") (name "Net-(U1-L)") (class "Default")
      (node (ref "L2") (pin "2") (pintype "passive"))
      (node (ref "U1") (pin "5") (pinfunction "L_5") (pintype "passive"))
    )
    (net (code "46") (name "Net-(U2-~{HOLD})") (class "Default")
      (node (ref "R7") (pin "1") (pintype "passive"))
      (node (ref "U2") (pin "7") (pinfunction "~{HOLD}_7") (pintype "passive"))
    )
    (net (code "47") (name "Net-(U2-~{WP}{slash}SIO2)") (class "Default")
      (node (ref "R16") (pin "1") (pintype "passive"))
      (node (ref "U2") (pin "3") (pinfunction "~{WP}/SIO2_3") (pintype "bidirectional"))
    )
    (net (code "48") (name "Net-(U3-2G4RF_IOP)") (class "Default")
      (node (ref "C2") (pin "1") (pintype "passive"))
      (node (ref "L1") (pin "1") (pintype "passive"))
      (node (ref "R1") (pin "1") (pintype "passive"))
      (node (ref "U3") (pin "17") (pinfunction "2G4RF_IOP_17") (pintype "passive"))
    )
    (net (code "49") (name "Net-(U3-AVDD)") (class "Default")
      (node (ref "C7") (pin "2") (pintype "passive"))
      (node (ref "C8") (pin "1") (pintype "passive"))
      (node (ref "R13") (pin "1") (pintype "passive"))
      (node (ref "U3") (pin "34") (pinfunction "AVDD_34") (pintype "power_in"))
    )
    (net (code "50") (name "Net-(U3-DECOUPLE)") (class "Default")
      (node (ref "C18") (pin "1") (pintype "passive"))
      (node (ref "U3") (pin "41") (pinfunction "DECOUPLE_41") (pintype "power_in"))
    )
    (net (code "51") (name "Net-(U3-HFXTAL_N)") (class "Default")
      (node (ref "U3") (pin "10") (pinfunction "HFXTAL_N_10") (pintype "passive"))
      (node (ref "X2") (pin "3") (pintype "passive"))
    )
    (net (code "52") (name "Net-(U3-HFXTAL_P)") (class "Default")
      (node (ref "U3") (pin "11") (pinfunction "HFXTAL_P_11") (pintype "passive"))
      (node (ref "X2") (pin "1") (pintype "passive"))
    )
    (net (code "53") (name "Net-(U3-PAVDD)") (class "Default")
      (node (ref "C10") (pin "1") (pintype "passive"))
      (node (ref "C9") (pin "1") (pintype "passive"))
      (node (ref "L4") (pin "1") (pintype "passive"))
      (node (ref "U3") (pin "18") (pinfunction "PAVDD_18") (pintype "power_in"))
    )
    (net (code "54") (name "Net-(U3-PB14)") (class "Default")
      (node (ref "U3") (pin "35") (pinfunction "PB14_35") (pintype "bidirectional"))
      (node (ref "X1") (pin "2") (pintype "passive"))
    )
    (net (code "55") (name "Net-(U3-PB15)") (class "Default")
      (node (ref "U3") (pin "36") (pinfunction "PB15_36") (pintype "bidirectional"))
      (node (ref "X1") (pin "1") (pintype "passive"))
    )
    (net (code "56") (name "Net-(U3-VREGSW)") (class "Default")
      (node (ref "L5") (pin "2") (pintype "passive"))
      (node (ref "U3") (pin "38") (pinfunction "VREGSW_38") (pintype "power_in"))
    )
    (net (code "57") (name "VBST") (class "Default")
      (node (ref "C3") (pin "2") (pintype "passive"))
      (node (ref "LD1") (pin "4") (pinfunction "COM_A_4") (pintype "passive"))
      (node (ref "R2") (pin "1") (pintype "passive"))
      (node (ref "U1") (pin "2") (pinfunction "FB_2") (pintype "passive"))
      (node (ref "U1") (pin "4") (pinfunction "Vout_4") (pintype "power_in"))
    )
    (net (code "58") (name "VDCDC") (class "Default")
      (node (ref "C12") (pin "1") (pintype "passive"))
      (node (ref "C13") (pin "1") (pintype "passive"))
      (node (ref "C15") (pin "2") (pintype "passive"))
      (node (ref "C17") (pin "1") (pintype "passive"))
      (node (ref "L5") (pin "1") (pintype "passive"))
      (node (ref "R20") (pin "1") (pintype "passive"))
      (node (ref "U3") (pin "40") (pinfunction "DVDD_40") (pintype "power_in"))
      (node (ref "U3") (pin "9") (pinfunction "RFVDD_9") (pintype "power_in"))
    )
    (net (code "59") (name "VDD") (class "Default")
      (node (ref "C16") (pin "2") (pintype "passive"))
      (node (ref "C19") (pin "1") (pintype "passive"))
      (node (ref "C20") (pin "1") (pintype "passive"))
      (node (ref "C21") (pin "1") (pintype "passive"))
      (node (ref "C4") (pin "2") (pintype "passive"))
      (node (ref "C5") (pin "1") (pintype "passive"))
      (node (ref "FB1") (pin "1") (pintype "passive"))
      (node (ref "J2") (pin "1") (pinfunction "1_1") (pintype "passive"))
      (node (ref "J3") (pin "3") (pinfunction "3_3") (pintype "passive"))
      (node (ref "J4") (pin "1") (pinfunction "VAEM_1") (pintype "passive"))
      (node (ref "L2") (pin "1") (pintype "passive"))
      (node (ref "L3") (pin "2") (pintype "passive"))
      (node (ref "L4") (pin "2") (pintype "passive"))
      (node (ref "Q1") (pin "2") (pinfunction "E_2") (pintype "passive"))
      (node (ref "R16") (pin "2") (pintype "passive"))
      (node (ref "R19") (pin "2") (pintype "passive"))
      (node (ref "R2") (pin "2") (pintype "passive"))
      (node (ref "R20") (pin "2") (pintype "passive"))
      (node (ref "R21") (pin "2") (pintype "passive"))
      (node (ref "R24") (pin "1") (pintype "passive"))
      (node (ref "R25") (pin "2") (pintype "passive"))
      (node (ref "R7") (pin "2") (pintype "passive"))
      (node (ref "U1") (pin "1") (pinfunction "Vin_1") (pintype "passive"))
      (node (ref "U2") (pin "8") (pinfunction "VCC_8") (pintype "power_in"))
      (node (ref "U3") (pin "39") (pinfunction "VREGVDD_39") (pintype "power_in"))
      (node (ref "U3") (pin "42") (pinfunction "IOVDD_42") (pintype "power_in"))
    )
    (net (code "60") (name "unconnected-(U3-NC-Pad13)") (class "Default")
      (node (ref "U3") (pin "13") (pinfunction "NC_13") (pintype "power_in"))
    )
    (net (code "61") (name "unconnected-(U3-PA5-Pad30)") (class "Default")
      (node (ref "U3") (pin "30") (pinfunction "PA5_30") (pintype "bidirectional"))
    )
    (net (code "62") (name "unconnected-(U3-PB11-Pad31)") (class "Default")
      (node (ref "U3") (pin "31") (pinfunction "PB11_31") (pintype "bidirectional"))
    )
    (net (code "63") (name "unconnected-(U3-PB12-Pad32)") (class "Default")
      (node (ref "U3") (pin "32") (pinfunction "PB12_32") (pintype "bidirectional"))
    )
    (net (code "64") (name "unconnected-(U3-PB13-Pad33)") (class "Default")
      (node (ref "U3") (pin "33") (pinfunction "PB13_33") (pintype "bidirectional"))
    )
    (net (code "65") (name "unconnected-(U3-PC8-Pad45)") (class "Default")
      (node (ref "U3") (pin "45") (pinfunction "PC8_45") (pintype "bidirectional"))
    )
    (net (code "66") (name "unconnected-(U3-PC9-Pad46)") (class "Default")
      (node (ref "U3") (pin "46") (pinfunction "PC9_46") (pintype "bidirectional"))
    )
    (net (code "67") (name "unconnected-(U3-PD10-Pad19)") (class "Default")
      (node (ref "U3") (pin "19") (pinfunction "PD10_19") (pintype "bidirectional"))
    )
    (net (code "68") (name "unconnected-(U3-PD11-Pad20)") (class "Default")
      (node (ref "U3") (pin "20") (pinfunction "PD11_20") (pintype "bidirectional"))
    )
  )
)
